# InputDigital.net
KiCad netlist of a schematic drawn in Altium Designer
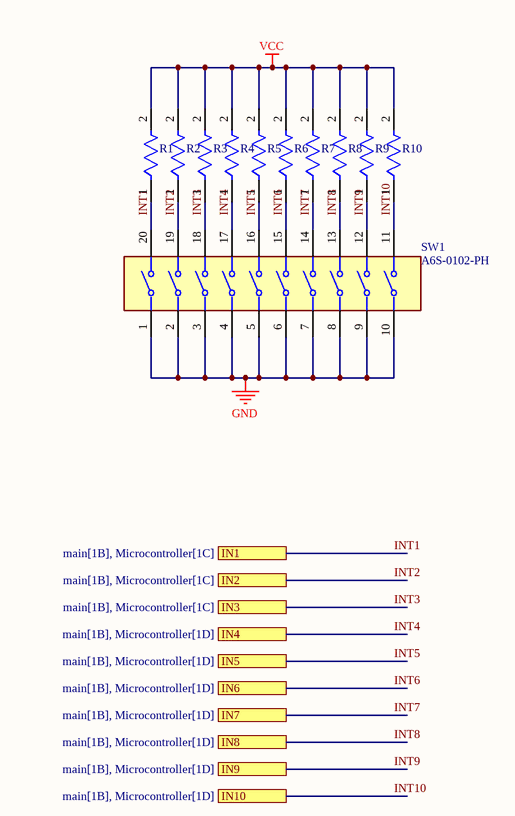
[diagram p0: InputDigital.SchDoc]

(export (version "E")
  (design (tool "Eeschema 10.0.6"))
  (components
    (comp (ref "R1")
      (value "RT0805BRD07249RL")
      (footprint "FP-RT0805-MFG")
      (description "RES SMD 249 OHM 0.1% 1/8W 0805")
      (fields
        (field (name "OCTOPART") "https://octopart.com/rt0805brd07249rl-yageo-1410573")
        (field (name "MANUFACTURER") "Yageo")
      )
      (libsource (lib "Ejemplo2") (part "CMP-03412-035801-1"))
    )
    (comp (ref "R2")
      (value "RT0805BRD07249RL")
      (footprint "FP-RT0805-MFG")
      (description "RES SMD 249 OHM 0.1% 1/8W 0805")
      (fields
        (field (name "OCTOPART") "https://octopart.com/rt0805brd07249rl-yageo-1410573")
        (field (name "MANUFACTURER") "Yageo")
      )
      (libsource (lib "Ejemplo2") (part "CMP-03412-035801-1"))
    )
    (comp (ref "R3")
      (value "RT0805BRD07249RL")
      (footprint "FP-RT0805-MFG")
      (description "RES SMD 249 OHM 0.1% 1/8W 0805")
      (fields
        (field (name "OCTOPART") "https://octopart.com/rt0805brd07249rl-yageo-1410573")
        (field (name "MANUFACTURER") "Yageo")
      )
      (libsource (lib "Ejemplo2") (part "CMP-03412-035801-1"))
    )
    (comp (ref "R4")
      (value "RT0805BRD07249RL")
      (footprint "FP-RT0805-MFG")
      (description "RES SMD 249 OHM 0.1% 1/8W 0805")
      (fields
        (field (name "OCTOPART") "https://octopart.com/rt0805brd07249rl-yageo-1410573")
        (field (name "MANUFACTURER") "Yageo")
      )
      (libsource (lib "Ejemplo2") (part "CMP-03412-035801-1"))
    )
    (comp (ref "R5")
      (value "RT0805BRD07249RL")
      (footprint "FP-RT0805-MFG")
      (description "RES SMD 249 OHM 0.1% 1/8W 0805")
      (fields
        (field (name "OCTOPART") "https://octopart.com/rt0805brd07249rl-yageo-1410573")
        (field (name "MANUFACTURER") "Yageo")
      )
      (libsource (lib "Ejemplo2") (part "CMP-03412-035801-1"))
    )
    (comp (ref "R6")
      (value "RT0805BRD07249RL")
      (footprint "FP-RT0805-MFG")
      (description "RES SMD 249 OHM 0.1% 1/8W 0805")
      (fields
        (field (name "OCTOPART") "https://octopart.com/rt0805brd07249rl-yageo-1410573")
        (field (name "MANUFACTURER") "Yageo")
      )
      (libsource (lib "Ejemplo2") (part "CMP-03412-035801-1"))
    )
    (comp (ref "R7")
      (value "RT0805BRD07249RL")
      (footprint "FP-RT0805-MFG")
      (description "RES SMD 249 OHM 0.1% 1/8W 0805")
      (fields
        (field (name "OCTOPART") "https://octopart.com/rt0805brd07249rl-yageo-1410573")
        (field (name "MANUFACTURER") "Yageo")
      )
      (libsource (lib "Ejemplo2") (part "CMP-03412-035801-1"))
    )
    (comp (ref "R8")
      (value "RT0805BRD07249RL")
      (footprint "FP-RT0805-MFG")
      (description "RES SMD 249 OHM 0.1% 1/8W 0805")
      (fields
        (field (name "OCTOPART") "https://octopart.com/rt0805brd07249rl-yageo-1410573")
        (field (name "MANUFACTURER") "Yageo")
      )
      (libsource (lib "Ejemplo2") (part "CMP-03412-035801-1"))
    )
    (comp (ref "R9")
      (value "RT0805BRD07249RL")
      (footprint "FP-RT0805-MFG")
      (description "RES SMD 249 OHM 0.1% 1/8W 0805")
      (fields
        (field (name "OCTOPART") "https://octopart.com/rt0805brd07249rl-yageo-1410573")
        (field (name "MANUFACTURER") "Yageo")
      )
      (libsource (lib "Ejemplo2") (part "CMP-03412-035801-1"))
    )
    (comp (ref "R10")
      (value "RT0805BRD07249RL")
      (footprint "FP-RT0805-MFG")
      (description "RES SMD 249 OHM 0.1% 1/8W 0805")
      (fields
        (field (name "OCTOPART") "https://octopart.com/rt0805brd07249rl-yageo-1410573")
        (field (name "MANUFACTURER") "Yageo")
      )
      (libsource (lib "Ejemplo2") (part "CMP-03412-035801-1"))
    )
    (comp (ref "SW1")
      (value "A6S-0102-PH")
      (footprint "FP-A6S-0102-PH-MFG")
      (description "SWITCH SLIDE DIP SPST 25MA 24V")
      (libsource (lib "Ejemplo2") (part "CMP-08827-000074-1"))
    )
  )
  (nets
    (net (code "1") (name "/INT1") (class "Default")
      (node (ref "R1") (pin "1") (pinfunction "1_1") (pintype "passive"))
      (node (ref "SW1") (pin "20") (pinfunction "20_20") (pintype "passive"))
    )
    (net (code "2") (name "/INT2") (class "Default")
      (node (ref "R2") (pin "1") (pinfunction "1_1") (pintype "passive"))
      (node (ref "SW1") (pin "19") (pinfunction "19_19") (pintype "passive"))
    )
    (net (code "3") (name "/INT3") (class "Default")
      (node (ref "R3") (pin "1") (pinfunction "1_1") (pintype "passive"))
      (node (ref "SW1") (pin "18") (pinfunction "18_18") (pintype "passive"))
    )
    (net (code "4") (name "/INT4") (class "Default")
      (node (ref "R4") (pin "1") (pinfunction "1_1") (pintype "passive"))
      (node (ref "SW1") (pin "17") (pinfunction "17_17") (pintype "passive"))
    )
    (net (code "5") (name "/INT5") (class "Default")
      (node (ref "R5") (pin "1") (pinfunction "1_1") (pintype "passive"))
      (node (ref "SW1") (pin "16") (pinfunction "16_16") (pintype "passive"))
    )
    (net (code "6") (name "/INT6") (class "Default")
      (node (ref "R6") (pin "1") (pinfunction "1_1") (pintype "passive"))
      (node (ref "SW1") (pin "15") (pinfunction "15_15") (pintype "passive"))
    )
    (net (code "7") (name "/INT7") (class "Default")
      (node (ref "R7") (pin "1") (pinfunction "1_1") (pintype "passive"))
      (node (ref "SW1") (pin "14") (pinfunction "14_14") (pintype "passive"))
    )
    (net (code "8") (name "/INT8") (class "Default")
      (node (ref "R8") (pin "1") (pinfunction "1_1") (pintype "passive"))
      (node (ref "SW1") (pin "13") (pinfunction "13_13") (pintype "passive"))
    )
    (net (code "9") (name "/INT9") (class "Default")
      (node (ref "R9") (pin "1") (pinfunction "1_1") (pintype "passive"))
      (node (ref "SW1") (pin "12") (pinfunction "12_12") (pintype "passive"))
    )
    (net (code "10") (name "/INT10") (class "Default")
      (node (ref "R10") (pin "1") (pinfunction "1_1") (pintype "passive"))
      (node (ref "SW1") (pin "11") (pinfunction "11_11") (pintype "passive"))
    )
    (net (code "11") (name "GND") (class "Default")
      (node (ref "SW1") (pin "1") (pinfunction "1_1") (pintype "passive"))
      (node (ref "SW1") (pin "10") (pinfunction "10_10") (pintype "passive"))
      (node (ref "SW1") (pin "2") (pinfunction "2_2") (pintype "passive"))
      (node (ref "SW1") (pin "3") (pinfunction "3_3") (pintype "passive"))
      (node (ref "SW1") (pin "4") (pinfunction "4_4") (pintype "passive"))
      (node (ref "SW1") (pin "5") (pinfunction "5_5") (pintype "passive"))
      (node (ref "SW1") (pin "6") (pinfunction "6_6") (pintype "passive"))
      (node (ref "SW1") (pin "7") (pinfunction "7_7") (pintype "passive"))
      (node (ref "SW1") (pin "8") (pinfunction "8_8") (pintype "passive"))
      (node (ref "SW1") (pin "9") (pinfunction "9_9") (pintype "passive"))
    )
    (net (code "12") (name "VCC") (class "Default")
      (node (ref "R1") (pin "2") (pinfunction "2_2") (pintype "passive"))
      (node (ref "R10") (pin "2") (pinfunction "2_2") (pintype "passive"))
      (node (ref "R2") (pin "2") (pinfunction "2_2") (pintype "passive"))
      (node (ref "R3") (pin "2") (pinfunction "2_2") (pintype "passive"))
      (node (ref "R4") (pin "2") (pinfunction "2_2") (pintype "passive"))
      (node (ref "R5") (pin "2") (pinfunction "2_2") (pintype "passive"))
      (node (ref "R6") (pin "2") (pinfunction "2_2") (pintype "passive"))
      (node (ref "R7") (pin "2") (pinfunction "2_2") (pintype "passive"))
      (node (ref "R8") (pin "2") (pinfunction "2_2") (pintype "passive"))
      (node (ref "R9") (pin "2") (pinfunction "2_2") (pintype "passive"))
    )
  )
)
